# MCU_DLS.net
KiCad netlist of a schematic drawn in Altium Designer
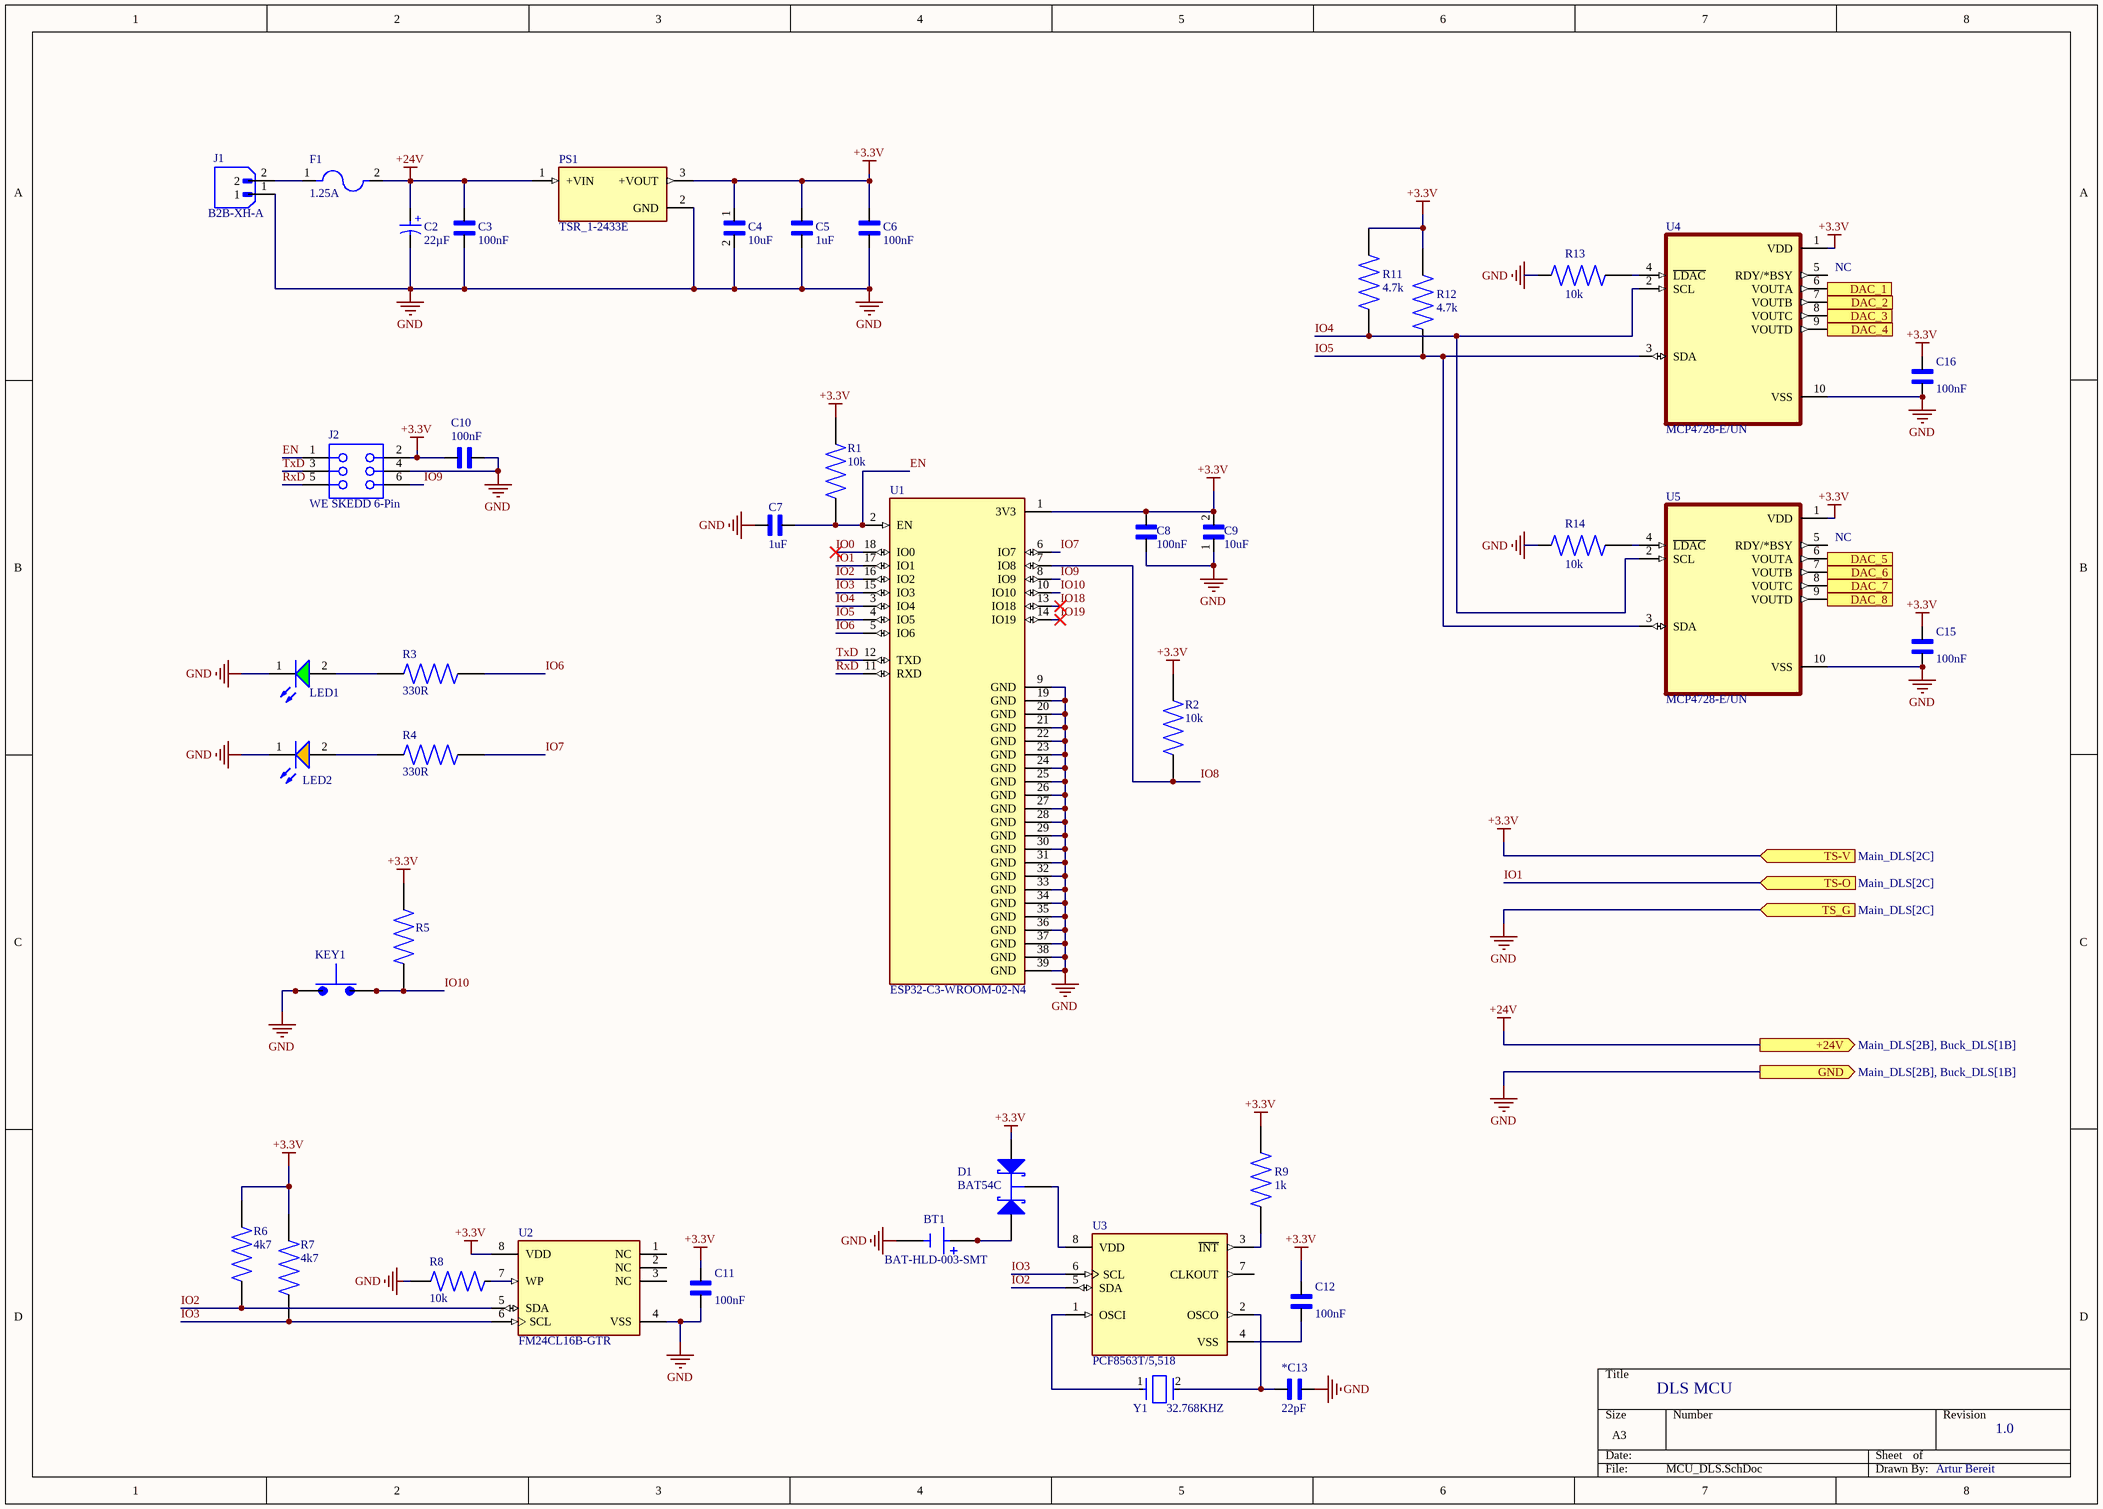
[diagram p0: MCU_DLS.SchDoc]

(export (version "E")
  (design (tool "Eeschema 10.0.6"))
  (components
    (comp (ref "*C13")
      (value "22pF")
      (footprint "CAPC2012X94N")
      (description "Capacitor;Ceramic;0.1uF;10%;50V;Tape/Reel ¦ AVX 08055C104KAT2A")
      (fields (field (name "MF") "AVX") (field (name "MP") "08055C104KAT2A"))
      (libsource (lib "") (part "08055C104KAT2A_1"))
    )
    (comp (ref "BT1")
      (value "BAT-HLD-003-SMT")
      (footprint "BAT_BAT-HLD-003-SMT")
      (description "Battery Holder Coin 20 SMT Nickel")
      (fields (field (name "MF") "Linx Technologies Inc."))
      (libsource (lib "BAT-HLD-003-SMT") (part "BAT-HLD-003-SMT"))
    )
    (comp (ref "C2")
      (value "22µF")
      (footprint "WCAP-ATG5_D5H11")
      (description "WCAP-ATG5 Aluminum Electrolytic Capacitor, Radial, THT, D5 x H11mm, 22µF, 50V")
      (fields
        (field (name "MANUFACTURER PART NUMBER") "860020672011")
        (field (name "MANUFACTURER") "Wurth Elektronik")
      )
      (libsource (lib "Altium_WCAP-ATG5+(rev22d)") (part "860020672011"))
    )
    (comp (ref "C3")
      (value "100nF")
      (footprint "CAPC2012X94N")
      (description "Capacitor;Ceramic;0.1uF;10%;50V;Tape/Reel ¦ AVX 08055C104KAT2A")
      (fields (field (name "MF") "AVX") (field (name "MP") "08055C104KAT2A"))
      (libsource (lib "08055C104KAT2A") (part "08055C104KAT2A"))
    )
    (comp (ref "C4")
      (value "10uF")
      (footprint "CAPC2012X145N")
      (fields (field (name "MP") "GCG21BR70J106KE01L"))
      (libsource (lib "GCG21BR70J106KE01L") (part "GCG21BR70J106KE01L"))
    )
    (comp (ref "C5")
      (value "1uF")
      (footprint "CAPC2012X140N")
      (description "SMD capacitor X7R(EIA) with capacitance 1.0uF Tol.10%. Rated voltage 16Vdc 125C")
      (fields (field (name "MF") "Murata") (field (name "MP") "GCM21BR71C105KA58L"))
      (libsource (lib "") (part "GCM21BR71C105KA58L_1"))
    )
    (comp (ref "C6")
      (value "100nF")
      (footprint "CAPC2012X94N")
      (description "Capacitor;Ceramic;0.1uF;10%;50V;Tape/Reel ¦ AVX 08055C104KAT2A")
      (fields (field (name "MF") "AVX") (field (name "MP") "08055C104KAT2A"))
      (libsource (lib "") (part "08055C104KAT2A_2"))
    )
    (comp (ref "C7")
      (value "1uF")
      (footprint "CAPC2012X140N")
      (description "SMD capacitor X7R(EIA) with capacitance 1.0uF Tol.10%. Rated voltage 16Vdc 125C")
      (fields (field (name "MF") "Murata") (field (name "MP") "GCM21BR71C105KA58L"))
      (libsource (lib "GCM21BR71C105KA58L") (part "GCM21BR71C105KA58L"))
    )
    (comp (ref "C8")
      (value "100nF")
      (footprint "CAPC2012X94N")
      (description "Capacitor;Ceramic;0.1uF;10%;50V;Tape/Reel ¦ AVX 08055C104KAT2A")
      (fields (field (name "MF") "AVX") (field (name "MP") "08055C104KAT2A"))
      (libsource (lib "08055C104KAT2A") (part "08055C104KAT2A"))
    )
    (comp (ref "C9")
      (value "10uF")
      (footprint "CAPC2012X145N")
      (fields (field (name "MP") "GRJ21BR61E106KE01K"))
      (libsource (lib "GRJ21BR61E106KE01K") (part "GRJ21BR61E106KE01K"))
    )
    (comp (ref "C10")
      (value "100nF")
      (footprint "CAPC2012X94N")
      (description "Capacitor;Ceramic;0.1uF;10%;50V;Tape/Reel ¦ AVX 08055C104KAT2A")
      (fields (field (name "MF") "AVX") (field (name "MP") "08055C104KAT2A"))
      (libsource (lib "") (part "08055C104KAT2A_3"))
    )
    (comp (ref "C11")
      (value "100nF")
      (footprint "CAPC2012X94N")
      (description "Capacitor;Ceramic;0.1uF;10%;50V;Tape/Reel ¦ AVX 08055C104KAT2A")
      (fields (field (name "MF") "AVX") (field (name "MP") "08055C104KAT2A"))
      (libsource (lib "08055C104KAT2A") (part "08055C104KAT2A"))
    )
    (comp (ref "C12")
      (value "100nF")
      (footprint "CAPC2012X94N")
      (description "Capacitor;Ceramic;0.1uF;10%;50V;Tape/Reel ¦ AVX 08055C104KAT2A")
      (fields (field (name "MF") "AVX") (field (name "MP") "08055C104KAT2A"))
      (libsource (lib "08055C104KAT2A") (part "08055C104KAT2A"))
    )
    (comp (ref "C15")
      (value "100nF")
      (footprint "CAPC2012X94N")
      (description "Capacitor;Ceramic;0.1uF;10%;50V;Tape/Reel ¦ AVX 08055C104KAT2A")
      (fields (field (name "MF") "AVX") (field (name "MP") "08055C104KAT2A"))
      (libsource (lib "08055C104KAT2A") (part "08055C104KAT2A"))
    )
    (comp (ref "C16")
      (value "100nF")
      (footprint "CAPC2012X94N")
      (description "Capacitor;Ceramic;0.1uF;10%;50V;Tape/Reel ¦ AVX 08055C104KAT2A")
      (fields (field (name "MF") "AVX") (field (name "MP") "08055C104KAT2A"))
      (libsource (lib "08055C104KAT2A") (part "08055C104KAT2A"))
    )
    (comp (ref "D1")
      (value "BAT54C")
      (footprint "NXP-SOT23-3_V")
      (description "Schottky Barrier Diode, 30 V, 2 uA, -55 to 150 degC, 3-Pin SOT23, RoHS, Tape and Reel")
      (fields (field (name "MANUFACTURER") "NXP Semiconductors"))
      (libsource (lib "Altium Content Vault") (part "NXP-DSKY_A1A2K3-3"))
    )
    (comp (ref "F1")
      (value "1.25A")
      (footprint "FUSC6125X279N")
      (description "2410 SMT Fuse ¦ Quick Acting ¦ 250mA ¦ Higher AC Voltage")
      (fields (field (name "MP") "0679L1250-01"))
      (libsource (lib "0679L1250-01") (part "0679L1250-01"))
    )
    (comp (ref "J1")
      (value "B2B-XH-A")
      (footprint "JST_B2B-XH-A_(LF)(SN)")
      (description "Connector Header Through Hole 2 position 0.098 (2.50mm)")
      (fields (field (name "MF") "JST Sales") (field (name "MP") "B2B-XH-A (LF)(SN)"))
      (libsource (lib "B2B-XH-A__LF__SN_") (part "B2B-XH-A_(LF)(SN)"))
    )
    (comp (ref "J2")
      (value "WE SKEDD 6-Pin")
      (footprint "490107670612_Permanent Application")
      (description "490107670612")
      (libsource (lib "Altium Content Vault") (part "Header_Female_2R_06P"))
    )
    (comp (ref "KEY1")
      (value "SKRPABE010")
      (footprint "SW_SKRPABE010")
      (description "Switch Tactile N.O. SPST Button J-Bend 0.05A 16VDC 1.57N SMD Automotive T/R")
      (fields (field (name "MF") "ALPS"))
      (libsource (lib "SKRPABE010") (part "SKRPABE010"))
    )
    (comp (ref "LED1")
      (value "Green")
      (footprint "WL-SMCW_0805_150080xx75000")
      (description "WL-SMCW Mono-color Chip LED Waterclear, SMT, size 0805, Green, 3.2V, 140°")
      (fields
        (field (name "MANUFACTURER PART NUMBER") "150080GS75000")
        (field (name "MANUFACTURER") "Wurth Elektronik")
      )
      (libsource (lib "Altium_WL-SMCW+(rev24b)") (part "150080GS75000"))
    )
    (comp (ref "LED2")
      (value "Amber, 2V, 140°")
      (footprint "WL-SMCW_0805_150080xx75000")
      (description "WL-SMCW Mono-color Chip LED Waterclear, SMT, size 0805, Amber, 2V, 140°")
      (fields
        (field (name "MANUFACTURER PART NUMBER") "150080AS75000")
        (field (name "MANUFACTURER") "Wurth Elektronik")
      )
      (libsource (lib "Altium_WL-SMCW+(rev24b)") (part "150080AS75000"))
    )
    (comp (ref "PS1")
      (value "TSR_1-2433E")
      (footprint "CONV_TSR_1-2433E")
      (fields (field (name "MF") "Traco Power") (field (name "MP") "TSR 1-2433E"))
      (libsource (lib "TSR_1-2433E") (part "TSR_1-2433E"))
    )
    (comp (ref "R1")
      (value "10k")
      (footprint "RES_ERJ6ENF1002V")
      (description "10 kOhms Â±1% 0.125W, 1/8W Chip Resistor 0805 (2012 Metric) Automotive AEC-Q200 Thick Film")
      (fields (field (name "MF") "Panasonic") (field (name "DIGI-KEY_PART_NUMBER") "P10.0KCCT-ND"))
      (libsource (lib "ERJ6ENF1002V") (part "ERJ6ENF1002V"))
    )
    (comp (ref "R2")
      (value "10k")
      (footprint "RES_ERJ6ENF1002V")
      (description "10 kOhms Â±1% 0.125W, 1/8W Chip Resistor 0805 (2012 Metric) Automotive AEC-Q200 Thick Film")
      (fields (field (name "MF") "Panasonic") (field (name "DIGI-KEY_PART_NUMBER") "P10.0KCCT-ND"))
      (libsource (lib "ERJ6ENF1002V") (part "ERJ6ENF1002V"))
    )
    (comp (ref "R3")
      (value "330R")
      (footprint "RES_ERJ6ENF1002V")
      (description "330Ohms Â±1% 0.125W, 1/8W Chip Resistor 0805 (2012 Metric) Automotive AEC-Q200 Thick Film")
      (fields (field (name "MF") "Panasonic") (field (name "DIGI-KEY_PART_NUMBER") "P10.0KCCT-ND"))
      (libsource (lib "ERJ6ENF1002V") (part "ERJ6ENF1002V"))
    )
    (comp (ref "R4")
      (value "330R")
      (footprint "RES_ERJ6ENF1002V")
      (description "330R Â±1% 0.125W, 1/8W Chip Resistor 0805 (2012 Metric) Automotive AEC-Q200 Thick Film")
      (fields (field (name "MF") "Panasonic") (field (name "DIGI-KEY_PART_NUMBER") "P10.0KCCT-ND"))
      (libsource (lib "ERJ6ENF1002V") (part "ERJ6ENF1002V"))
    )
    (comp (ref "R5")
      (value "ERJ6ENF1002V")
      (footprint "RES_ERJ6ENF1002V")
      (description "10 kOhms Â±1% 0.125W, 1/8W Chip Resistor 0805 (2012 Metric) Automotive AEC-Q200 Thick Film")
      (fields (field (name "MF") "Panasonic") (field (name "DIGI-KEY_PART_NUMBER") "P10.0KCCT-ND"))
      (libsource (lib "ERJ6ENF1002V") (part "ERJ6ENF1002V"))
    )
    (comp (ref "R6")
      (value "4k7")
      (footprint "RES_ERJ6ENF1002V")
      (description "10 kOhms Â±1% 0.125W, 1/8W Chip Resistor 0805 (2012 Metric) Automotive AEC-Q200 Thick Film")
      (fields (field (name "MF") "Panasonic") (field (name "DIGI-KEY_PART_NUMBER") "P10.0KCCT-ND"))
      (libsource (lib "ERJ6ENF1002V") (part "ERJ6ENF1002V"))
    )
    (comp (ref "R7")
      (value "4k7")
      (footprint "RES_ERJ6ENF1002V")
      (description "10 kOhms Â±1% 0.125W, 1/8W Chip Resistor 0805 (2012 Metric) Automotive AEC-Q200 Thick Film")
      (fields (field (name "MF") "Panasonic") (field (name "DIGI-KEY_PART_NUMBER") "P10.0KCCT-ND"))
      (libsource (lib "ERJ6ENF1002V") (part "ERJ6ENF1002V"))
    )
    (comp (ref "R8")
      (value "10k")
      (footprint "RES_ERJ6ENF1002V")
      (description "10 kOhms Â±1% 0.125W, 1/8W Chip Resistor 0805 (2012 Metric) Automotive AEC-Q200 Thick Film")
      (fields (field (name "MF") "Panasonic") (field (name "DIGI-KEY_PART_NUMBER") "P10.0KCCT-ND"))
      (libsource (lib "ERJ6ENF1002V") (part "ERJ6ENF1002V"))
    )
    (comp (ref "R9")
      (value "1k")
      (footprint "RES_ERJ6ENF1002V")
      (description "1 kOhms Â±1% 0.125W, 1/8W Chip Resistor 0805 (2012 Metric) Automotive AEC-Q200 Thick Film")
      (fields (field (name "MF") "Panasonic") (field (name "DIGI-KEY_PART_NUMBER") "P10.0KCCT-ND"))
      (libsource (lib "ERJ6ENF1002V") (part "ERJ6ENF1002V"))
    )
    (comp (ref "R11")
      (value "4.7k")
      (footprint "RES_ERJ6ENF1002V")
      (description "10 kOhms Â±1% 0.125W, 1/8W Chip Resistor 0805 (2012 Metric) Automotive AEC-Q200 Thick Film")
      (fields (field (name "MF") "Panasonic") (field (name "DIGI-KEY_PART_NUMBER") "P10.0KCCT-ND"))
      (libsource (lib "ERJ6ENF1002V") (part "ERJ6ENF1002V"))
    )
    (comp (ref "R12")
      (value "4.7k")
      (footprint "RES_ERJ6ENF1002V")
      (description "10 kOhms Â±1% 0.125W, 1/8W Chip Resistor 0805 (2012 Metric) Automotive AEC-Q200 Thick Film")
      (fields (field (name "MF") "Panasonic") (field (name "DIGI-KEY_PART_NUMBER") "P10.0KCCT-ND"))
      (libsource (lib "ERJ6ENF1002V") (part "ERJ6ENF1002V"))
    )
    (comp (ref "R13")
      (value "10k")
      (footprint "RES_ERJ6ENF1002V")
      (description "10 kOhms Â±1% 0.125W, 1/8W Chip Resistor 0805 (2012 Metric) Automotive AEC-Q200 Thick Film")
      (fields (field (name "MF") "Panasonic") (field (name "DIGI-KEY_PART_NUMBER") "P10.0KCCT-ND"))
      (libsource (lib "ERJ6ENF1002V") (part "ERJ6ENF1002V"))
    )
    (comp (ref "R14")
      (value "10k")
      (footprint "RES_ERJ6ENF1002V")
      (description "10 kOhms Â±1% 0.125W, 1/8W Chip Resistor 0805 (2012 Metric) Automotive AEC-Q200 Thick Film")
      (fields (field (name "MF") "Panasonic") (field (name "DIGI-KEY_PART_NUMBER") "P10.0KCCT-ND"))
      (libsource (lib "ERJ6ENF1002V") (part "ERJ6ENF1002V"))
    )
    (comp (ref "U1")
      (value "ESP32-C3-WROOM-02-N4")
      (footprint "MODULE_ESP32-C3-WROOM-02-H4")
      (fields (field (name "MF") "Espressif Systems"))
      (libsource (lib "ESP32-C3-WROOM-02-N4") (part "ESP32-C3-WROOM-02-N4"))
    )
    (comp (ref "U2")
      (value "FM24CL16B-GTR")
      (footprint "FP-51-85066-MFG")
      (description "IC FRAM 16K I2C 1MHZ 8SOIC")
      (libsource (lib "Altium Content Vault") (part "4718bdacb8c7ac14bb45e4a6a15b88f"))
    )
    (comp (ref "U3")
      (value "PCF8563T/5,518")
      (footprint "FP-SOT96-1-MFG")
      (description "IC RTC CLK/CALENDAR I2C 8-SOIC")
      (fields
        (field (name "OCTOPART") "https://octopart.com/pcf8563t%2F5%2C518-nxp+semiconductors-19647995")
        (field (name "MANUFACTURER") "NXP")
      )
      (libsource (lib "Altium Content Vault") (part "a37bc7bf6ae0839037c7f5583b0f96f"))
    )
    (comp (ref "U4")
      (value "MCP4728-E/UN")
      (footprint "SOP50P490X110-10N")
      (description "Microchip 4-channel 12 bit Serial DAC 10-Pin MSOP ¦ Microchip Technology Inc. MCP4728-E/UN")
      (fields (field (name "MF") "Microchip"))
      (libsource (lib "MCP4728-E_UN") (part "MCP4728-E/UN"))
    )
    (comp (ref "U5")
      (value "MCP4728-E/UN")
      (footprint "SOP50P490X110-10N")
      (description "Microchip 4-channel 12 bit Serial DAC 10-Pin MSOP ¦ Microchip Technology Inc. MCP4728-E/UN")
      (fields (field (name "MF") "Microchip"))
      (libsource (lib "MCP4728-E_UN") (part "MCP4728-E/UN"))
    )
    (comp (ref "Y1")
      (value "32.768KHZ")
      (footprint "FP-ABS07-MFG")
      (description "Crystal 32.768kHz ±20ppm (Tol) 7pF FUND 70kΩ 2-Pin CSMD T/R")
      (fields (field (name "TOLERANCE") "20ppm"))
      (libsource (lib "Altium Content Vault") (part "c23a69dc6c9e2f18f2079038eb95dd1"))
    )
  )
  (nets
    (net (code "1") (name "+3.3V") (class "Default")
      (node (ref "C10") (pin "1") (pinfunction "1_1") (pintype "passive"))
      (node (ref "C11") (pin "2") (pinfunction "2_2") (pintype "passive"))
      (node (ref "C12") (pin "2") (pinfunction "2_2") (pintype "passive"))
      (node (ref "C15") (pin "2") (pinfunction "2_2") (pintype "passive"))
      (node (ref "C16") (pin "2") (pinfunction "2_2") (pintype "passive"))
      (node (ref "C4") (pin "1") (pinfunction "1_1") (pintype "passive"))
      (node (ref "C5") (pin "2") (pinfunction "2_2") (pintype "passive"))
      (node (ref "C6") (pin "1") (pinfunction "1_1") (pintype "passive"))
      (node (ref "C8") (pin "2") (pinfunction "2_2") (pintype "passive"))
      (node (ref "C9") (pin "2") (pinfunction "2_2") (pintype "passive"))
      (node (ref "D1") (pin "1") (pinfunction "A_1") (pintype "passive"))
      (node (ref "J2") (pin "2") (pinfunction "2_2") (pintype "passive"))
      (node (ref "PS1") (pin "3") (pinfunction "+VOUT_3") (pintype "output"))
      (node (ref "R1") (pin "2") (pinfunction "2_2") (pintype "passive"))
      (node (ref "R11") (pin "1") (pinfunction "1_1") (pintype "passive"))
      (node (ref "R12") (pin "1") (pinfunction "1_1") (pintype "passive"))
      (node (ref "R2") (pin "2") (pinfunction "2_2") (pintype "passive"))
      (node (ref "R5") (pin "2") (pinfunction "2_2") (pintype "passive"))
      (node (ref "R6") (pin "1") (pinfunction "1_1") (pintype "passive"))
      (node (ref "R7") (pin "2") (pinfunction "2_2") (pintype "passive"))
      (node (ref "R9") (pin "2") (pinfunction "2_2") (pintype "passive"))
      (node (ref "U1") (pin "1") (pinfunction "3V3_1") (pintype "power_in"))
      (node (ref "U2") (pin "8") (pinfunction "VDD_8") (pintype "power_in"))
      (node (ref "U4") (pin "1") (pinfunction "VDD_1") (pintype "power_in"))
      (node (ref "U5") (pin "1") (pinfunction "VDD_1") (pintype "power_in"))
    )
    (net (code "2") (name "+24V") (class "Default")
      (node (ref "C2") (pin "1") (pinfunction "P_1") (pintype "passive"))
      (node (ref "C3") (pin "2") (pinfunction "2_2") (pintype "passive"))
      (node (ref "F1") (pin "2") (pinfunction "2_2") (pintype "passive"))
      (node (ref "PS1") (pin "1") (pinfunction "+VIN_1") (pintype "input"))
    )
    (net (code "3") (name "/DAC_1") (class "Default")
      (node (ref "U4") (pin "6") (pinfunction "VOUTA_6") (pintype "output"))
    )
    (net (code "4") (name "/DAC_2") (class "Default")
      (node (ref "U4") (pin "7") (pinfunction "VOUTB_7") (pintype "output"))
    )
    (net (code "5") (name "/DAC_3") (class "Default")
      (node (ref "U4") (pin "8") (pinfunction "VOUTC_8") (pintype "output"))
    )
    (net (code "6") (name "/DAC_4") (class "Default")
      (node (ref "U4") (pin "9") (pinfunction "VOUTD_9") (pintype "output"))
    )
    (net (code "7") (name "/DAC_5") (class "Default")
      (node (ref "U5") (pin "6") (pinfunction "VOUTA_6") (pintype "output"))
    )
    (net (code "8") (name "/DAC_6") (class "Default")
      (node (ref "U5") (pin "7") (pinfunction "VOUTB_7") (pintype "output"))
    )
    (net (code "9") (name "/DAC_7") (class "Default")
      (node (ref "U5") (pin "8") (pinfunction "VOUTC_8") (pintype "output"))
    )
    (net (code "10") (name "/DAC_8") (class "Default")
      (node (ref "U5") (pin "9") (pinfunction "VOUTD_9") (pintype "output"))
    )
    (net (code "11") (name "/EN") (class "Default")
      (node (ref "C7") (pin "2") (pinfunction "2_2") (pintype "passive"))
      (node (ref "J2") (pin "1") (pinfunction "1_1") (pintype "passive"))
      (node (ref "R1") (pin "1") (pinfunction "1_1") (pintype "passive"))
      (node (ref "U1") (pin "2") (pinfunction "EN_2") (pintype "input"))
    )
    (net (code "12") (name "/IO0") (class "Default")
      (node (ref "U1") (pin "18") (pinfunction "IO0_18") (pintype "bidirectional+no_connect"))
    )
    (net (code "13") (name "/IO1") (class "Default")
      (node (ref "U1") (pin "17") (pinfunction "IO1_17") (pintype "bidirectional"))
    )
    (net (code "14") (name "/IO2") (class "Default")
      (node (ref "R6") (pin "2") (pinfunction "2_2") (pintype "passive"))
      (node (ref "U1") (pin "16") (pinfunction "IO2_16") (pintype "bidirectional"))
      (node (ref "U2") (pin "5") (pinfunction "SDA_5") (pintype "bidirectional"))
      (node (ref "U3") (pin "5") (pinfunction "SDA_5") (pintype "bidirectional"))
    )
    (net (code "15") (name "/IO3") (class "Default")
      (node (ref "R7") (pin "1") (pinfunction "1_1") (pintype "passive"))
      (node (ref "U1") (pin "15") (pinfunction "IO3_15") (pintype "bidirectional"))
      (node (ref "U2") (pin "6") (pinfunction "SCL_6") (pintype "input"))
      (node (ref "U3") (pin "6") (pinfunction "SCL_6") (pintype "input"))
    )
    (net (code "16") (name "/IO4") (class "Default")
      (node (ref "R11") (pin "2") (pinfunction "2_2") (pintype "passive"))
      (node (ref "U1") (pin "3") (pinfunction "IO4_3") (pintype "bidirectional"))
      (node (ref "U4") (pin "2") (pinfunction "SCL_2") (pintype "input"))
      (node (ref "U5") (pin "2") (pinfunction "SCL_2") (pintype "input"))
    )
    (net (code "17") (name "/IO5") (class "Default")
      (node (ref "R12") (pin "2") (pinfunction "2_2") (pintype "passive"))
      (node (ref "U1") (pin "4") (pinfunction "IO5_4") (pintype "bidirectional"))
      (node (ref "U4") (pin "3") (pinfunction "SDA_3") (pintype "bidirectional"))
      (node (ref "U5") (pin "3") (pinfunction "SDA_3") (pintype "bidirectional"))
    )
    (net (code "18") (name "/IO6") (class "Default")
      (node (ref "R3") (pin "2") (pinfunction "2_2") (pintype "passive"))
      (node (ref "U1") (pin "5") (pinfunction "IO6_5") (pintype "bidirectional"))
    )
    (net (code "19") (name "/IO7") (class "Default")
      (node (ref "R4") (pin "2") (pinfunction "2_2") (pintype "passive"))
      (node (ref "U1") (pin "6") (pinfunction "IO7_6") (pintype "bidirectional"))
    )
    (net (code "20") (name "/IO8") (class "Default")
      (node (ref "R2") (pin "1") (pinfunction "1_1") (pintype "passive"))
      (node (ref "U1") (pin "7") (pinfunction "IO8_7") (pintype "bidirectional"))
    )
    (net (code "21") (name "/IO9") (class "Default")
      (node (ref "J2") (pin "6") (pinfunction "6_6") (pintype "passive"))
      (node (ref "U1") (pin "8") (pinfunction "IO9_8") (pintype "bidirectional"))
    )
    (net (code "22") (name "/IO10") (class "Default")
      (node (ref "KEY1") (pin "3") (pinfunction "2_3") (pintype "passive"))
      (node (ref "KEY1") (pin "4") (pinfunction "2_4") (pintype "passive"))
      (node (ref "R5") (pin "1") (pinfunction "1_1") (pintype "passive"))
      (node (ref "U1") (pin "10") (pinfunction "IO10_10") (pintype "bidirectional"))
    )
    (net (code "23") (name "/IO18") (class "Default")
      (node (ref "U1") (pin "13") (pinfunction "IO18_13") (pintype "bidirectional+no_connect"))
    )
    (net (code "24") (name "/IO19") (class "Default")
      (node (ref "U1") (pin "14") (pinfunction "IO19_14") (pintype "bidirectional+no_connect"))
    )
    (net (code "25") (name "/RxD") (class "Default")
      (node (ref "J2") (pin "5") (pinfunction "5_5") (pintype "passive"))
      (node (ref "U1") (pin "11") (pinfunction "RXD_11") (pintype "bidirectional"))
    )
    (net (code "26") (name "/TxD") (class "Default")
      (node (ref "J2") (pin "3") (pinfunction "3_3") (pintype "passive"))
      (node (ref "U1") (pin "12") (pinfunction "TXD_12") (pintype "bidirectional"))
    )
    (net (code "27") (name "GND") (class "Default")
      (node (ref "*C13") (pin "1") (pinfunction "1_1") (pintype "passive"))
      (node (ref "BT1") (pin "N") (pinfunction "NEG_N") (pintype "passive"))
      (node (ref "C10") (pin "2") (pinfunction "2_2") (pintype "passive"))
      (node (ref "C11") (pin "1") (pinfunction "1_1") (pintype "passive"))
      (node (ref "C15") (pin "1") (pinfunction "1_1") (pintype "passive"))
      (node (ref "C16") (pin "1") (pinfunction "1_1") (pintype "passive"))
      (node (ref "C2") (pin "2") (pinfunction "N_2") (pintype "passive"))
      (node (ref "C3") (pin "1") (pinfunction "1_1") (pintype "passive"))
      (node (ref "C4") (pin "2") (pinfunction "2_2") (pintype "passive"))
      (node (ref "C5") (pin "1") (pinfunction "1_1") (pintype "passive"))
      (node (ref "C6") (pin "2") (pinfunction "2_2") (pintype "passive"))
      (node (ref "C7") (pin "1") (pinfunction "1_1") (pintype "passive"))
      (node (ref "C8") (pin "1") (pinfunction "1_1") (pintype "passive"))
      (node (ref "C9") (pin "1") (pinfunction "1_1") (pintype "passive"))
      (node (ref "J1") (pin "1") (pinfunction "1_1") (pintype "passive"))
      (node (ref "J2") (pin "4") (pinfunction "4_4") (pintype "passive"))
      (node (ref "KEY1") (pin "1") (pinfunction "1_1") (pintype "passive"))
      (node (ref "KEY1") (pin "2") (pinfunction "1_2") (pintype "passive"))
      (node (ref "LED1") (pin "1") (pinfunction "K_1") (pintype "passive"))
      (node (ref "LED2") (pin "1") (pinfunction "K_1") (pintype "passive"))
      (node (ref "PS1") (pin "2") (pinfunction "GND_2") (pintype "power_in"))
      (node (ref "R13") (pin "2") (pinfunction "2_2") (pintype "passive"))
      (node (ref "R14") (pin "2") (pinfunction "2_2") (pintype "passive"))
      (node (ref "R8") (pin "1") (pinfunction "1_1") (pintype "passive"))
      (node (ref "U1") (pin "19") (pinfunction "GND_19") (pintype "power_in"))
      (node (ref "U1") (pin "20") (pinfunction "GND_20") (pintype "power_in"))
      (node (ref "U1") (pin "21") (pinfunction "GND_21") (pintype "power_in"))
      (node (ref "U1") (pin "22") (pinfunction "GND_22") (pintype "power_in"))
      (node (ref "U1") (pin "23") (pinfunction "GND_23") (pintype "power_in"))
      (node (ref "U1") (pin "24") (pinfunction "GND_24") (pintype "power_in"))
      (node (ref "U1") (pin "25") (pinfunction "GND_25") (pintype "power_in"))
      (node (ref "U1") (pin "26") (pinfunction "GND_26") (pintype "power_in"))
      (node (ref "U1") (pin "27") (pinfunction "GND_27") (pintype "power_in"))
      (node (ref "U1") (pin "28") (pinfunction "GND_28") (pintype "power_in"))
      (node (ref "U1") (pin "29") (pinfunction "GND_29") (pintype "power_in"))
      (node (ref "U1") (pin "30") (pinfunction "GND_30") (pintype "power_in"))
      (node (ref "U1") (pin "31") (pinfunction "GND_31") (pintype "power_in"))
      (node (ref "U1") (pin "32") (pinfunction "GND_32") (pintype "power_in"))
      (node (ref "U1") (pin "33") (pinfunction "GND_33") (pintype "power_in"))
      (node (ref "U1") (pin "34") (pinfunction "GND_34") (pintype "power_in"))
      (node (ref "U1") (pin "35") (pinfunction "GND_35") (pintype "power_in"))
      (node (ref "U1") (pin "36") (pinfunction "GND_36") (pintype "power_in"))
      (node (ref "U1") (pin "37") (pinfunction "GND_37") (pintype "power_in"))
      (node (ref "U1") (pin "38") (pinfunction "GND_38") (pintype "power_in"))
      (node (ref "U1") (pin "39") (pinfunction "GND_39") (pintype "power_in"))
      (node (ref "U1") (pin "9") (pinfunction "GND_9") (pintype "power_in"))
      (node (ref "U2") (pin "4") (pinfunction "VSS_4") (pintype "power_in"))
      (node (ref "U4") (pin "10") (pinfunction "VSS_10") (pintype "power_in"))
      (node (ref "U5") (pin "10") (pinfunction "VSS_10") (pintype "power_in"))
    )
    (net (code "28") (name "Net-(BT1-POS-PadP1)") (class "Default")
      (node (ref "BT1") (pin "P1") (pinfunction "POS_P1") (pintype "passive"))
      (node (ref "BT1") (pin "P2") (pinfunction "POS_P2") (pintype "passive"))
      (node (ref "D1") (pin "2") (pinfunction "A_2") (pintype "passive"))
    )
    (net (code "29") (name "Net-(D1-K)") (class "Default")
      (node (ref "D1") (pin "3") (pinfunction "K_3") (pintype "passive"))
      (node (ref "U3") (pin "8") (pinfunction "VDD_8") (pintype "power_in"))
    )
    (net (code "30") (name "Net-(F1-Pad1)") (class "Default")
      (node (ref "F1") (pin "1") (pinfunction "1_1") (pintype "passive"))
      (node (ref "J1") (pin "2") (pinfunction "2_2") (pintype "passive"))
    )
    (net (code "31") (name "Net-(LED1-A)") (class "Default")
      (node (ref "LED1") (pin "2") (pinfunction "A_2") (pintype "passive"))
      (node (ref "R3") (pin "1") (pinfunction "1_1") (pintype "passive"))
    )
    (net (code "32") (name "Net-(LED2-A)") (class "Default")
      (node (ref "LED2") (pin "2") (pinfunction "A_2") (pintype "passive"))
      (node (ref "R4") (pin "1") (pinfunction "1_1") (pintype "passive"))
    )
    (net (code "33") (name "Net-(U2-WP)") (class "Default")
      (node (ref "R8") (pin "2") (pinfunction "2_2") (pintype "passive"))
      (node (ref "U2") (pin "7") (pinfunction "WP_7") (pintype "input"))
    )
    (net (code "34") (name "Net-(U3-OSCI)") (class "Default")
      (node (ref "U3") (pin "1") (pinfunction "OSCI_1") (pintype "input"))
      (node (ref "Y1") (pin "1") (pinfunction "1_1") (pintype "passive"))
    )
    (net (code "35") (name "Net-(U3-OSCO)") (class "Default")
      (node (ref "*C13") (pin "2") (pinfunction "2_2") (pintype "passive"))
      (node (ref "U3") (pin "2") (pinfunction "OSCO_2") (pintype "output"))
      (node (ref "Y1") (pin "2") (pinfunction "2_2") (pintype "passive"))
    )
    (net (code "36") (name "Net-(U3-VSS)") (class "Default")
      (node (ref "C12") (pin "1") (pinfunction "1_1") (pintype "passive"))
      (node (ref "U3") (pin "4") (pinfunction "VSS_4") (pintype "power_in"))
    )
    (net (code "37") (name "Net-(U3-~{INT})") (class "Default")
      (node (ref "R9") (pin "1") (pinfunction "1_1") (pintype "passive"))
      (node (ref "U3") (pin "3") (pinfunction "~{INT}_3") (pintype "output"))
    )
    (net (code "38") (name "Net-(U4-~{LDAC})") (class "Default")
      (node (ref "R13") (pin "1") (pinfunction "1_1") (pintype "passive"))
      (node (ref "U4") (pin "4") (pinfunction "~{LDAC}_4") (pintype "input"))
    )
    (net (code "39") (name "Net-(U5-~{LDAC})") (class "Default")
      (node (ref "R14") (pin "1") (pinfunction "1_1") (pintype "passive"))
      (node (ref "U5") (pin "4") (pinfunction "~{LDAC}_4") (pintype "input"))
    )
    (net (code "40") (name "unconnected-(U2-NC-Pad1)") (class "Default")
      (node (ref "U2") (pin "1") (pinfunction "NC_1") (pintype "passive"))
    )
    (net (code "41") (name "unconnected-(U2-NC-Pad2)") (class "Default")
      (node (ref "U2") (pin "2") (pinfunction "NC_2") (pintype "passive"))
    )
    (net (code "42") (name "unconnected-(U2-NC-Pad3)") (class "Default")
      (node (ref "U2") (pin "3") (pinfunction "NC_3") (pintype "passive"))
    )
    (net (code "43") (name "unconnected-(U3-CLKOUT-Pad7)") (class "Default")
      (node (ref "U3") (pin "7") (pinfunction "CLKOUT_7") (pintype "output"))
    )
    (net (code "44") (name "unconnected-(U4-RDY{slash}*BSY-Pad5)") (class "Default")
      (node (ref "U4") (pin "5") (pinfunction "RDY/*BSY_5") (pintype "output"))
    )
    (net (code "45") (name "unconnected-(U5-RDY{slash}*BSY-Pad5)") (class "Default")
      (node (ref "U5") (pin "5") (pinfunction "RDY/*BSY_5") (pintype "output"))
    )
  )
)
